# untitled.net
KiCad netlist of a schematic drawn in EAGLE
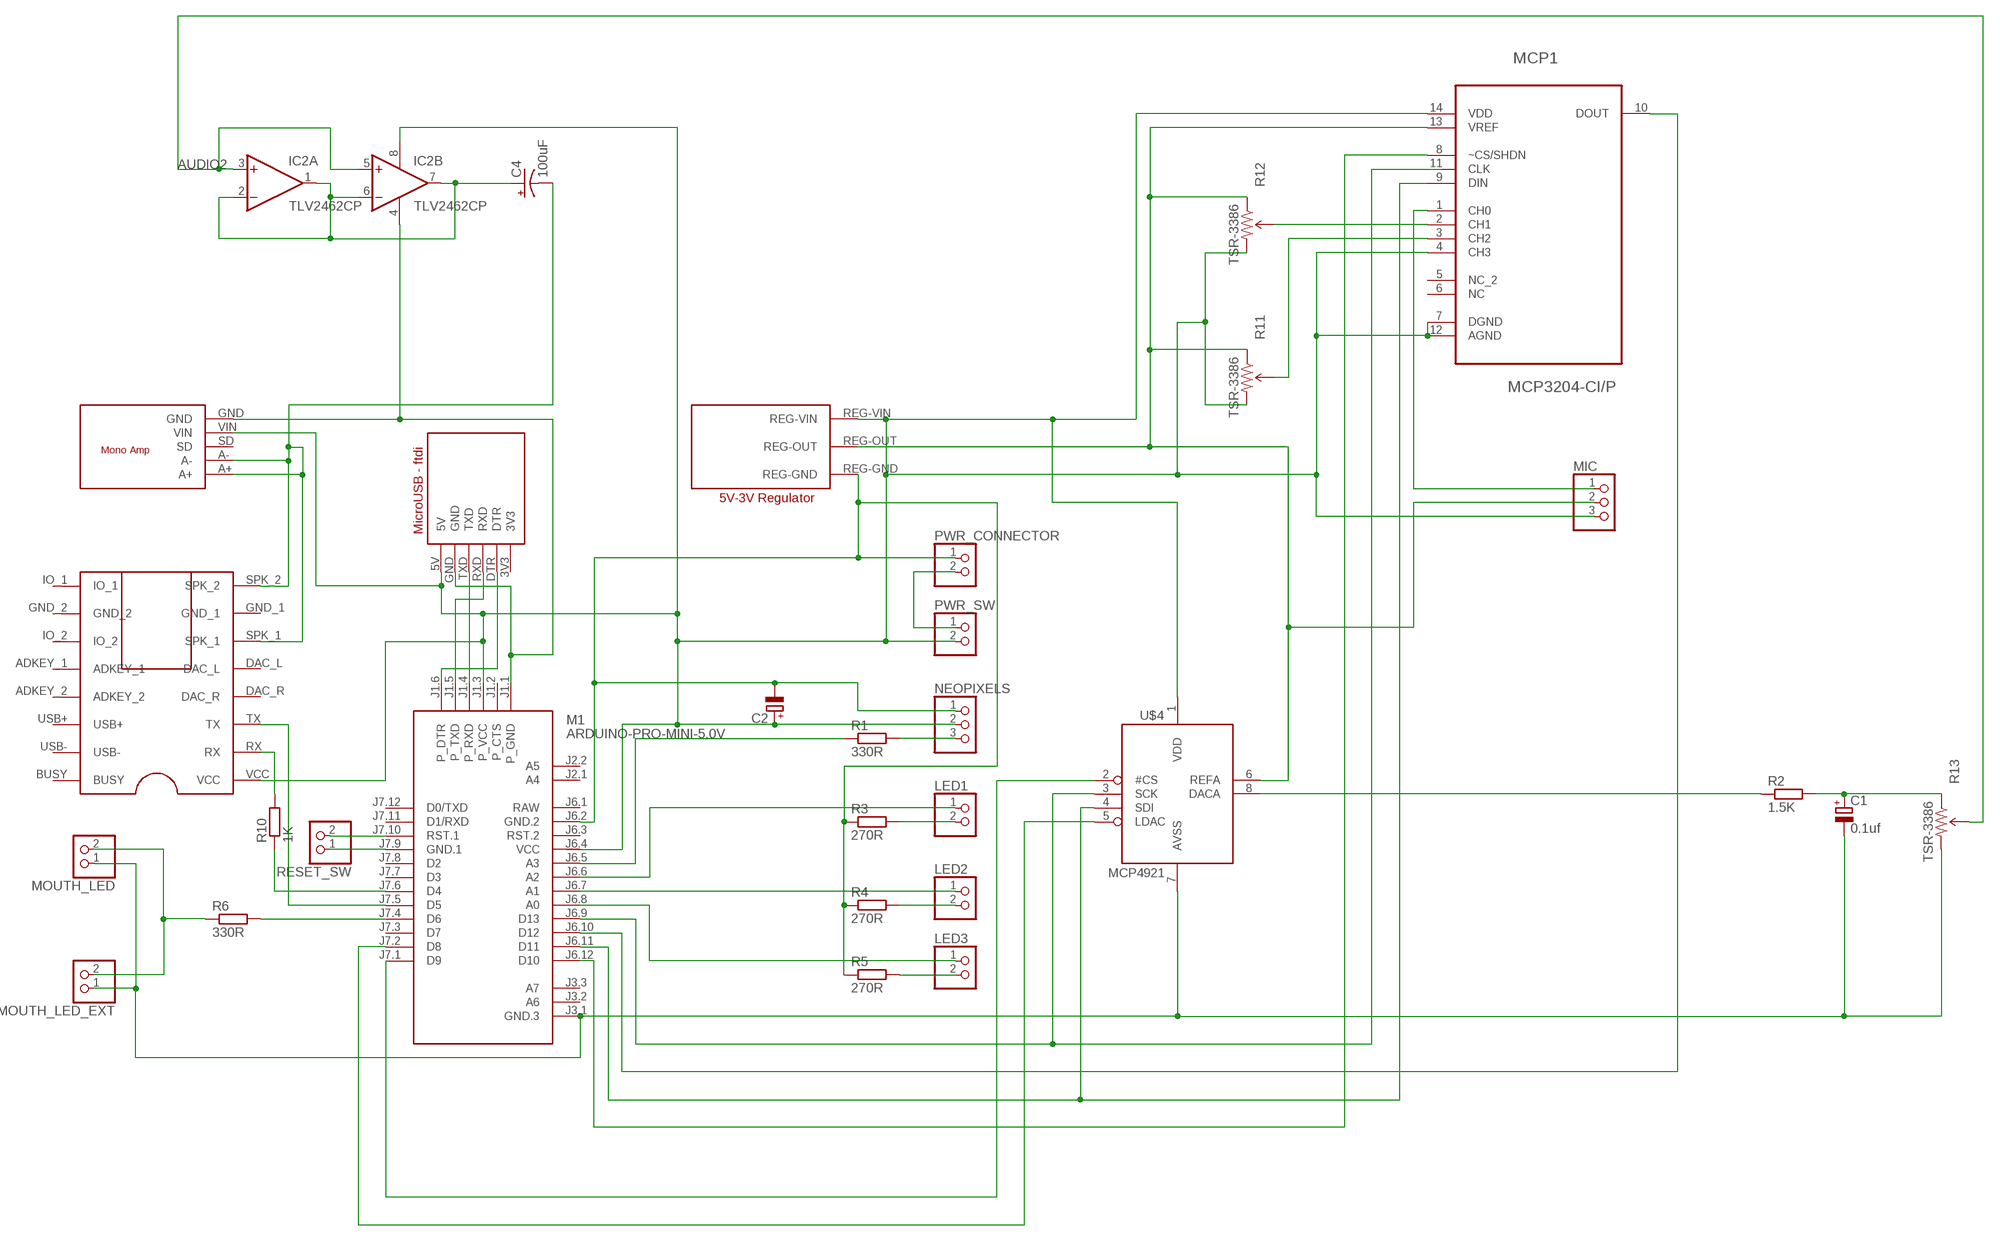
[diagram p0: schematic, sheet 1]

(export (version "E")
  (design (tool "Eeschema 10.0.6"))
  (components
    (comp (ref "C1")
      (value "0.1uf")
      (footprint "eagle-import:E2,5-6E")
      (libsource (lib "eagle-import") (part "CPOL-EUE2,5-6E"))
    )
    (comp (ref "C2")
      (value "CPOL-EUE2,5-6E")
      (footprint "eagle-import:E2,5-6E")
      (libsource (lib "eagle-import") (part "CPOL-EUE2,5-6E"))
    )
    (comp (ref "C4")
      (value "100uF")
      (footprint "eagle-import:CPOL-RADIAL-100UF-25V")
      (libsource (lib "eagle-import") (part "CAP_POLPTH1"))
    )
    (comp (ref "IC2")
      (value "TLV2462CP")
      (footprint "eagle-import:DIL08")
      (libsource (lib "eagle-import") (part "TL072P"))
    )
    (comp (ref "LED1")
      (value "PINHD-1X2")
      (footprint "eagle-import:1X02")
      (libsource (lib "eagle-import") (part "PINHD-1X2"))
    )
    (comp (ref "LED2")
      (value "PINHD-1X2")
      (footprint "eagle-import:1X02")
      (libsource (lib "eagle-import") (part "PINHD-1X2"))
    )
    (comp (ref "LED3")
      (value "PINHD-1X2")
      (footprint "eagle-import:1X02")
      (libsource (lib "eagle-import") (part "PINHD-1X2"))
    )
    (comp (ref "M1")
      (value "ARDUINO-PRO-MINI-5.0V")
      (footprint "eagle-import:ARDUINO-PRO-MINI")
      (libsource (lib "eagle-import") (part "ARDUINO-PRO-MINI-5.0V"))
    )
    (comp (ref "MCP1")
      (value "MCP3204-CI/P")
      (footprint "eagle-import:DIP254P762X432-14")
      (libsource (lib "eagle-import") (part "MCP3204-CI/P"))
    )
    (comp (ref "MIC")
      (value "PINHD-1X3")
      (footprint "eagle-import:1X03")
      (libsource (lib "eagle-import") (part "PINHD-1X3"))
    )
    (comp (ref "MOUTH_LED")
      (value "PINHD-1X2")
      (footprint "eagle-import:1X02")
      (libsource (lib "eagle-import") (part "PINHD-1X2"))
    )
    (comp (ref "MOUTH_LED_EXT")
      (value "PINHD-1X2")
      (footprint "eagle-import:1X02")
      (libsource (lib "eagle-import") (part "PINHD-1X2"))
    )
    (comp (ref "NEOPIXELS")
      (value "PINHD-1X3")
      (footprint "eagle-import:1X03")
      (libsource (lib "eagle-import") (part "PINHD-1X3"))
    )
    (comp (ref "PWR_CONNECTOR")
      (value "PINHD-1X2")
      (footprint "eagle-import:1X02")
      (libsource (lib "eagle-import") (part "PINHD-1X2"))
    )
    (comp (ref "PWR_SW")
      (value "PINHD-1X2")
      (footprint "eagle-import:1X02")
      (libsource (lib "eagle-import") (part "PINHD-1X2"))
    )
    (comp (ref "R1")
      (value "330R")
      (footprint "eagle-import:0207_7")
      (libsource (lib "eagle-import") (part "R-EU_0207/7"))
    )
    (comp (ref "R2")
      (value "1.5K")
      (footprint "eagle-import:0207_7")
      (libsource (lib "eagle-import") (part "R-EU_0207/7"))
    )
    (comp (ref "R3")
      (value "270R")
      (footprint "eagle-import:0207_7")
      (libsource (lib "eagle-import") (part "R-EU_0207/7"))
    )
    (comp (ref "R4")
      (value "270R")
      (footprint "eagle-import:0207_7")
      (libsource (lib "eagle-import") (part "R-EU_0207/7"))
    )
    (comp (ref "R5")
      (value "270R")
      (footprint "eagle-import:0207_7")
      (libsource (lib "eagle-import") (part "R-EU_0207/7"))
    )
    (comp (ref "R6")
      (value "330R")
      (footprint "eagle-import:0207_7")
      (libsource (lib "eagle-import") (part "R-EU_0207/7"))
    )
    (comp (ref "R10")
      (value "1K")
      (footprint "eagle-import:0207_7")
      (libsource (lib "eagle-import") (part "R-EU_0207/7"))
    )
    (comp (ref "R11")
      (value "TSR-3386")
      (footprint "eagle-import:3386U")
      (libsource (lib "eagle-import") (part "TRIMPOT-PTH-KNOB"))
    )
    (comp (ref "R12")
      (value "TSR-3386")
      (footprint "eagle-import:3386U")
      (libsource (lib "eagle-import") (part "TRIMPOT-PTH-KNOB"))
    )
    (comp (ref "R13")
      (value "TSR-3386")
      (footprint "eagle-import:3386U")
      (libsource (lib "eagle-import") (part "TRIMPOT-PTH-KNOB"))
    )
    (comp (ref "RESET_SW")
      (value "PINHD-1X2")
      (footprint "eagle-import:1X02")
      (libsource (lib "eagle-import") (part "PINHD-1X2"))
    )
    (comp (ref "U$1")
      (value "DPLAYER-MINI-DEV")
      (footprint "eagle-import:DPLAYER-MINI-PAC")
      (libsource (lib "eagle-import") (part "DPLAYER-MINI-DEV"))
    )
    (comp (ref "U$2")
      (value "MICRO-USB-DEV")
      (footprint "eagle-import:MICRO-USB-PAC")
      (libsource (lib "eagle-import") (part "MICRO-USB-DEV"))
    )
    (comp (ref "U$4")
      (value "MCP4921")
      (footprint "eagle-import:DIL08")
      (libsource (lib "eagle-import") (part "MCP4921"))
    )
    (comp (ref "U$5")
      (value "5V-TO-3V-REG-DEV")
      (footprint "eagle-import:5V-TO-3V-REG-PAC")
      (libsource (lib "eagle-import") (part "5V-TO-3V-REG-DEV"))
    )
    (comp (ref "U$6")
      (value "MONO-AMP-DEV")
      (footprint "eagle-import:MONO-AMP-PAC")
      (libsource (lib "eagle-import") (part "MONO-AMP-DEV"))
    )
  )
  (nets
    (net (code "1") (name "/3V3") (class "Default")
      (node (ref "U$2") (pin "3V3") (pinfunction "3V3_3V3") (pintype "power_in"))
    )
    (net (code "2") (name "/AUDIO2") (class "Default")
      (node (ref "IC2") (pin "3") (pinfunction "+IN_3") (pintype "input"))
      (node (ref "IC2") (pin "5") (pinfunction "+IN_5") (pintype "input"))
      (node (ref "R13") (pin "2") (pinfunction "WIPER_2") (pintype "passive"))
    )
    (net (code "3") (name "/GND_1") (class "Default")
      (node (ref "U$1") (pin "GND_1") (pinfunction "GND_1_GND_1") (pintype "power_in"))
    )
    (net (code "4") (name "/GND_2") (class "Default")
      (node (ref "U$1") (pin "GND_2") (pinfunction "GND_2_GND_2") (pintype "power_in"))
    )
    (net (code "5") (name "/RAW") (class "Default")
      (node (ref "M1") (pin "J6.1") (pinfunction "RAW_J6.1") (pintype "power_in"))
    )
    (net (code "6") (name "/VCC") (class "Default")
      (node (ref "M1") (pin "J6.4") (pinfunction "VCC_J6.4") (pintype "power_in"))
    )
    (net (code "7") (name "Net-(C4-+)") (class "Default")
      (node (ref "C4") (pin "1") (pinfunction "+_1") (pintype "passive"))
      (node (ref "IC2") (pin "1") (pinfunction "OUT_1") (pintype "output"))
      (node (ref "IC2") (pin "2") (pinfunction "-IN_2") (pintype "input"))
      (node (ref "IC2") (pin "6") (pinfunction "-IN_6") (pintype "input"))
      (node (ref "IC2") (pin "7") (pinfunction "OUT_7") (pintype "output"))
    )
    (net (code "8") (name "Net-(C4--)") (class "Default")
      (node (ref "C4") (pin "2") (pinfunction "-_2") (pintype "passive"))
      (node (ref "U$1") (pin "SPK_1") (pinfunction "SPK_1_SPK_1") (pintype "bidirectional"))
      (node (ref "U$1") (pin "SPK_2") (pinfunction "SPK_2_SPK_2") (pintype "bidirectional"))
      (node (ref "U$6") (pin "A+") (pinfunction "A+_A+") (pintype "input"))
      (node (ref "U$6") (pin "A-") (pinfunction "A-_A-") (pintype "input"))
    )
    (net (code "9") (name "Net-(IC2C-V+)") (class "Default")
      (node (ref "C2") (pin "+") (pinfunction "+_+") (pintype "passive"))
      (node (ref "IC2") (pin "8") (pinfunction "V+_8") (pintype "power_in"))
      (node (ref "M1") (pin "J1.3") (pinfunction "P_VCC_J1.3") (pintype "bidirectional"))
      (node (ref "MCP1") (pin "12") (pinfunction "AGND_12") (pintype "passive"))
      (node (ref "MCP1") (pin "14") (pinfunction "VDD_14") (pintype "power_in"))
      (node (ref "MCP1") (pin "4") (pinfunction "CH3_4") (pintype "input"))
      (node (ref "MCP1") (pin "7") (pinfunction "DGND_7") (pintype "passive"))
      (node (ref "MIC") (pin "3") (pinfunction "3_3") (pintype "passive"))
      (node (ref "NEOPIXELS") (pin "2") (pinfunction "2_2") (pintype "passive"))
      (node (ref "PWR_SW") (pin "2") (pinfunction "2_2") (pintype "passive"))
      (node (ref "R11") (pin "3") (pinfunction "CW_3") (pintype "passive"))
      (node (ref "R12") (pin "3") (pinfunction "CW_3") (pintype "passive"))
      (node (ref "U$1") (pin "VCC") (pinfunction "VCC_VCC") (pintype "power_in"))
      (node (ref "U$2") (pin "5V") (pinfunction "5V_5V") (pintype "power_in"))
      (node (ref "U$4") (pin "1") (pinfunction "VDD_1") (pintype "power_in"))
      (node (ref "U$5") (pin "REG-VIN") (pinfunction "REG-VIN_REG-VIN") (pintype "power_in"))
      (node (ref "U$6") (pin "VIN") (pinfunction "VIN_VIN") (pintype "power_in"))
    )
    (net (code "10") (name "Net-(IC2C-V-)") (class "Default")
      (node (ref "IC2") (pin "4") (pinfunction "V-_4") (pintype "power_in"))
      (node (ref "M1") (pin "J1.1") (pinfunction "P_GND_J1.1") (pintype "bidirectional"))
      (node (ref "U$2") (pin "GND") (pinfunction "GND_GND") (pintype "bidirectional"))
      (node (ref "U$6") (pin "GND") (pinfunction "GND_GND") (pintype "power_in"))
    )
    (net (code "11") (name "Net-(LED1-Pad2)") (class "Default")
      (node (ref "LED1") (pin "2") (pinfunction "2_2") (pintype "passive"))
      (node (ref "R3") (pin "2") (pinfunction "2_2") (pintype "passive"))
    )
    (net (code "12") (name "Net-(LED2-Pad2)") (class "Default")
      (node (ref "LED2") (pin "2") (pinfunction "2_2") (pintype "passive"))
      (node (ref "R4") (pin "2") (pinfunction "2_2") (pintype "passive"))
    )
    (net (code "13") (name "Net-(LED3-Pad2)") (class "Default")
      (node (ref "LED3") (pin "2") (pinfunction "2_2") (pintype "passive"))
      (node (ref "R5") (pin "2") (pinfunction "2_2") (pintype "passive"))
    )
    (net (code "14") (name "Net-(M1-A0)") (class "Default")
      (node (ref "LED3") (pin "1") (pinfunction "1_1") (pintype "passive"))
      (node (ref "M1") (pin "J6.8") (pinfunction "A0_J6.8") (pintype "bidirectional"))
    )
    (net (code "15") (name "Net-(M1-A1)") (class "Default")
      (node (ref "LED2") (pin "1") (pinfunction "1_1") (pintype "passive"))
      (node (ref "M1") (pin "J6.7") (pinfunction "A1_J6.7") (pintype "bidirectional"))
    )
    (net (code "16") (name "Net-(M1-A2)") (class "Default")
      (node (ref "LED1") (pin "1") (pinfunction "1_1") (pintype "passive"))
      (node (ref "M1") (pin "J6.6") (pinfunction "A2_J6.6") (pintype "bidirectional"))
    )
    (net (code "17") (name "Net-(M1-A3)") (class "Default")
      (node (ref "M1") (pin "J6.5") (pinfunction "A3_J6.5") (pintype "bidirectional"))
      (node (ref "R1") (pin "1") (pinfunction "1_1") (pintype "passive"))
    )
    (net (code "18") (name "Net-(M1-D4)") (class "Default")
      (node (ref "M1") (pin "J7.6") (pinfunction "D4_J7.6") (pintype "bidirectional"))
      (node (ref "R10") (pin "1") (pinfunction "1_1") (pintype "passive"))
    )
    (net (code "19") (name "Net-(M1-D5)") (class "Default")
      (node (ref "M1") (pin "J7.5") (pinfunction "D5_J7.5") (pintype "bidirectional"))
      (node (ref "U$1") (pin "TX") (pinfunction "TX_TX") (pintype "bidirectional"))
    )
    (net (code "20") (name "Net-(M1-D6)") (class "Default")
      (node (ref "M1") (pin "J7.4") (pinfunction "D6_J7.4") (pintype "bidirectional"))
      (node (ref "R6") (pin "2") (pinfunction "2_2") (pintype "passive"))
    )
    (net (code "21") (name "Net-(M1-D8)") (class "Default")
      (node (ref "M1") (pin "J7.2") (pinfunction "D8_J7.2") (pintype "bidirectional"))
      (node (ref "U$4") (pin "5") (pinfunction "LDAC_5") (pintype "input"))
    )
    (net (code "22") (name "Net-(M1-D9)") (class "Default")
      (node (ref "M1") (pin "J7.1") (pinfunction "D9_J7.1") (pintype "bidirectional"))
      (node (ref "U$4") (pin "2") (pinfunction "#CS_2") (pintype "input"))
    )
    (net (code "23") (name "Net-(M1-D10)") (class "Default")
      (node (ref "M1") (pin "J6.12") (pinfunction "D10_J6.12") (pintype "bidirectional"))
      (node (ref "MCP1") (pin "8") (pinfunction "~{CS/SHDN}_8") (pintype "input"))
    )
    (net (code "24") (name "Net-(M1-D11)") (class "Default")
      (node (ref "M1") (pin "J6.11") (pinfunction "D11_J6.11") (pintype "bidirectional"))
      (node (ref "MCP1") (pin "9") (pinfunction "DIN_9") (pintype "input"))
      (node (ref "U$4") (pin "4") (pinfunction "SDI_4") (pintype "input"))
    )
    (net (code "25") (name "Net-(M1-D12)") (class "Default")
      (node (ref "M1") (pin "J6.10") (pinfunction "D12_J6.10") (pintype "bidirectional"))
      (node (ref "MCP1") (pin "10") (pinfunction "DOUT_10") (pintype "output"))
    )
    (net (code "26") (name "Net-(M1-D13)") (class "Default")
      (node (ref "M1") (pin "J6.9") (pinfunction "D13_J6.9") (pintype "bidirectional"))
      (node (ref "U$4") (pin "3") (pinfunction "SCK_3") (pintype "input"))
    )
    (net (code "27") (name "Net-(M1-GND.1)") (class "Default")
      (node (ref "M1") (pin "J7.9") (pinfunction "GND.1_J7.9") (pintype "power_in"))
      (node (ref "RESET_SW") (pin "1") (pinfunction "1_1") (pintype "passive"))
    )
    (net (code "28") (name "Net-(M1-GND.2)") (class "Default")
      (node (ref "C2") (pin "-") (pinfunction "-_-") (pintype "passive"))
      (node (ref "M1") (pin "J6.2") (pinfunction "GND.2_J6.2") (pintype "power_in"))
      (node (ref "NEOPIXELS") (pin "1") (pinfunction "1_1") (pintype "passive"))
      (node (ref "PWR_CONNECTOR") (pin "1") (pinfunction "1_1") (pintype "passive"))
      (node (ref "R3") (pin "1") (pinfunction "1_1") (pintype "passive"))
      (node (ref "R4") (pin "1") (pinfunction "1_1") (pintype "passive"))
      (node (ref "R5") (pin "1") (pinfunction "1_1") (pintype "passive"))
      (node (ref "U$5") (pin "REG-GND") (pinfunction "REG-GND_REG-GND") (pintype "bidirectional"))
    )
    (net (code "29") (name "Net-(M1-GND.3)") (class "Default")
      (node (ref "C1") (pin "-") (pinfunction "-_-") (pintype "passive"))
      (node (ref "M1") (pin "J3.1") (pinfunction "GND.3_J3.1") (pintype "bidirectional"))
      (node (ref "MOUTH_LED") (pin "1") (pinfunction "1_1") (pintype "passive"))
      (node (ref "MOUTH_LED_EXT") (pin "1") (pinfunction "1_1") (pintype "passive"))
      (node (ref "R13") (pin "3") (pinfunction "CW_3") (pintype "passive"))
      (node (ref "U$4") (pin "7") (pinfunction "AVSS_7") (pintype "power_in"))
    )
    (net (code "30") (name "Net-(M1-P_DTR)") (class "Default")
      (node (ref "M1") (pin "J1.6") (pinfunction "P_DTR_J1.6") (pintype "bidirectional"))
      (node (ref "U$2") (pin "DTR") (pinfunction "DTR_DTR") (pintype "power_in"))
    )
    (net (code "31") (name "Net-(M1-P_RXD)") (class "Default")
      (node (ref "M1") (pin "J1.4") (pinfunction "P_RXD_J1.4") (pintype "bidirectional"))
      (node (ref "U$2") (pin "TXD") (pinfunction "TXD_TXD") (pintype "bidirectional"))
    )
    (net (code "32") (name "Net-(M1-P_TXD)") (class "Default")
      (node (ref "M1") (pin "J1.5") (pinfunction "P_TXD_J1.5") (pintype "bidirectional"))
      (node (ref "U$2") (pin "RXD") (pinfunction "RXD_RXD") (pintype "bidirectional"))
    )
    (net (code "33") (name "Net-(M1-RST.1)") (class "Default")
      (node (ref "M1") (pin "J7.10") (pinfunction "RST.1_J7.10") (pintype "bidirectional"))
      (node (ref "RESET_SW") (pin "2") (pinfunction "2_2") (pintype "passive"))
    )
    (net (code "34") (name "Net-(MCP1-CH0)") (class "Default")
      (node (ref "MCP1") (pin "1") (pinfunction "CH0_1") (pintype "input"))
      (node (ref "MIC") (pin "1") (pinfunction "1_1") (pintype "passive"))
    )
    (net (code "35") (name "Net-(MCP1-CH1)") (class "Default")
      (node (ref "MCP1") (pin "2") (pinfunction "CH1_2") (pintype "input"))
      (node (ref "R12") (pin "2") (pinfunction "WIPER_2") (pintype "passive"))
    )
    (net (code "36") (name "Net-(MCP1-CH2)") (class "Default")
      (node (ref "MCP1") (pin "3") (pinfunction "CH2_3") (pintype "input"))
      (node (ref "R11") (pin "2") (pinfunction "WIPER_2") (pintype "passive"))
    )
    (net (code "37") (name "Net-(MCP1-VREF)") (class "Default")
      (node (ref "MCP1") (pin "13") (pinfunction "VREF_13") (pintype "power_in"))
      (node (ref "MIC") (pin "2") (pinfunction "2_2") (pintype "passive"))
      (node (ref "R11") (pin "1") (pinfunction "CCW_1") (pintype "passive"))
      (node (ref "R12") (pin "1") (pinfunction "CCW_1") (pintype "passive"))
      (node (ref "U$4") (pin "6") (pinfunction "REFA_6") (pintype "input"))
      (node (ref "U$5") (pin "REG-OUT") (pinfunction "REG-OUT_REG-OUT") (pintype "power_in"))
    )
    (net (code "38") (name "Net-(MOUTH_LED-Pad2)") (class "Default")
      (node (ref "MOUTH_LED") (pin "2") (pinfunction "2_2") (pintype "passive"))
      (node (ref "MOUTH_LED_EXT") (pin "2") (pinfunction "2_2") (pintype "passive"))
      (node (ref "R6") (pin "1") (pinfunction "1_1") (pintype "passive"))
    )
    (net (code "39") (name "Net-(NEOPIXELS-Pad3)") (class "Default")
      (node (ref "NEOPIXELS") (pin "3") (pinfunction "3_3") (pintype "passive"))
      (node (ref "R1") (pin "2") (pinfunction "2_2") (pintype "passive"))
    )
    (net (code "40") (name "Net-(PWR_CONNECTOR-Pad2)") (class "Default")
      (node (ref "PWR_CONNECTOR") (pin "2") (pinfunction "2_2") (pintype "passive"))
      (node (ref "PWR_SW") (pin "1") (pinfunction "1_1") (pintype "passive"))
    )
    (net (code "41") (name "Net-(R10-Pad2)") (class "Default")
      (node (ref "R10") (pin "2") (pinfunction "2_2") (pintype "passive"))
      (node (ref "U$1") (pin "RX") (pinfunction "RX_RX") (pintype "bidirectional"))
    )
    (net (code "42") (name "Net-(R13-CCW)") (class "Default")
      (node (ref "C1") (pin "+") (pinfunction "+_+") (pintype "passive"))
      (node (ref "R13") (pin "1") (pinfunction "CCW_1") (pintype "passive"))
      (node (ref "R2") (pin "2") (pinfunction "2_2") (pintype "passive"))
    )
    (net (code "43") (name "Net-(U$4-DACA)") (class "Default")
      (node (ref "R2") (pin "1") (pinfunction "1_1") (pintype "passive"))
      (node (ref "U$4") (pin "8") (pinfunction "DACA_8") (pintype "output"))
    )
    (net (code "44") (name "unconnected-(M1-A4-PadJ2.1)") (class "Default")
      (node (ref "M1") (pin "J2.1") (pinfunction "A4_J2.1") (pintype "bidirectional"))
    )
    (net (code "45") (name "unconnected-(M1-A5-PadJ2.2)") (class "Default")
      (node (ref "M1") (pin "J2.2") (pinfunction "A5_J2.2") (pintype "bidirectional"))
    )
    (net (code "46") (name "unconnected-(M1-A6-PadJ3.2)") (class "Default")
      (node (ref "M1") (pin "J3.2") (pinfunction "A6_J3.2") (pintype "bidirectional"))
    )
    (net (code "47") (name "unconnected-(M1-A7-PadJ3.3)") (class "Default")
      (node (ref "M1") (pin "J3.3") (pinfunction "A7_J3.3") (pintype "bidirectional"))
    )
    (net (code "48") (name "unconnected-(M1-D0{slash}TXD-PadJ7.12)") (class "Default")
      (node (ref "M1") (pin "J7.12") (pinfunction "D0/TXD_J7.12") (pintype "bidirectional"))
    )
    (net (code "49") (name "unconnected-(M1-D1{slash}RXD-PadJ7.11)") (class "Default")
      (node (ref "M1") (pin "J7.11") (pinfunction "D1/RXD_J7.11") (pintype "bidirectional"))
    )
    (net (code "50") (name "unconnected-(M1-D2-PadJ7.8)") (class "Default")
      (node (ref "M1") (pin "J7.8") (pinfunction "D2_J7.8") (pintype "bidirectional"))
    )
    (net (code "51") (name "unconnected-(M1-D3-PadJ7.7)") (class "Default")
      (node (ref "M1") (pin "J7.7") (pinfunction "D3_J7.7") (pintype "bidirectional"))
    )
    (net (code "52") (name "unconnected-(M1-D7-PadJ7.3)") (class "Default")
      (node (ref "M1") (pin "J7.3") (pinfunction "D7_J7.3") (pintype "bidirectional"))
    )
    (net (code "53") (name "unconnected-(M1-P_CTS-PadJ1.2)") (class "Default")
      (node (ref "M1") (pin "J1.2") (pinfunction "P_CTS_J1.2") (pintype "bidirectional"))
    )
    (net (code "54") (name "unconnected-(M1-RST.2-PadJ6.3)") (class "Default")
      (node (ref "M1") (pin "J6.3") (pinfunction "RST.2_J6.3") (pintype "bidirectional"))
    )
    (net (code "55") (name "unconnected-(MCP1-CLK-Pad11)") (class "Default")
      (node (ref "MCP1") (pin "11") (pinfunction "CLK_11") (pintype "input"))
    )
    (net (code "56") (name "unconnected-(MCP1-NC-Pad6)") (class "Default")
      (node (ref "MCP1") (pin "6") (pinfunction "NC_6") (pintype "no_connect"))
    )
    (net (code "57") (name "unconnected-(MCP1-NC_2-Pad5)") (class "Default")
      (node (ref "MCP1") (pin "5") (pinfunction "NC_2_5") (pintype "no_connect"))
    )
    (net (code "58") (name "unconnected-(U$1-PadADKEY_1)") (class "Default")
      (node (ref "U$1") (pin "ADKEY_1") (pinfunction "ADKEY_1_ADKEY_1") (pintype "bidirectional"))
    )
    (net (code "59") (name "unconnected-(U$1-PadADKEY_2)") (class "Default")
      (node (ref "U$1") (pin "ADKEY_2") (pinfunction "ADKEY_2_ADKEY_2") (pintype "bidirectional"))
    )
    (net (code "60") (name "unconnected-(U$1-PadBUSY)") (class "Default")
      (node (ref "U$1") (pin "BUSY") (pinfunction "BUSY_BUSY") (pintype "bidirectional"))
    )
    (net (code "61") (name "unconnected-(U$1-PadDAC_L)") (class "Default")
      (node (ref "U$1") (pin "DAC_L") (pinfunction "DAC_L_DAC_L") (pintype "bidirectional"))
    )
    (net (code "62") (name "unconnected-(U$1-PadDAC_R)") (class "Default")
      (node (ref "U$1") (pin "DAC_R") (pinfunction "DAC_R_DAC_R") (pintype "bidirectional"))
    )
    (net (code "63") (name "unconnected-(U$1-PadIO_1)") (class "Default")
      (node (ref "U$1") (pin "IO_1") (pinfunction "IO_1_IO_1") (pintype "bidirectional"))
    )
    (net (code "64") (name "unconnected-(U$1-PadIO_2)") (class "Default")
      (node (ref "U$1") (pin "IO_2") (pinfunction "IO_2_IO_2") (pintype "bidirectional"))
    )
    (net (code "65") (name "unconnected-(U$1-PadUSB+)") (class "Default")
      (node (ref "U$1") (pin "USB+") (pinfunction "USB+_USB+") (pintype "bidirectional"))
    )
    (net (code "66") (name "unconnected-(U$1-PadUSB-)") (class "Default")
      (node (ref "U$1") (pin "USB-") (pinfunction "USB-_USB-") (pintype "bidirectional"))
    )
    (net (code "67") (name "unconnected-(U$6-PadSD)") (class "Default")
      (node (ref "U$6") (pin "SD") (pinfunction "SD_SD") (pintype "input"))
    )
  )
)
